# DisplayShieldV2.net
KiCad netlist of a schematic drawn in EAGLE
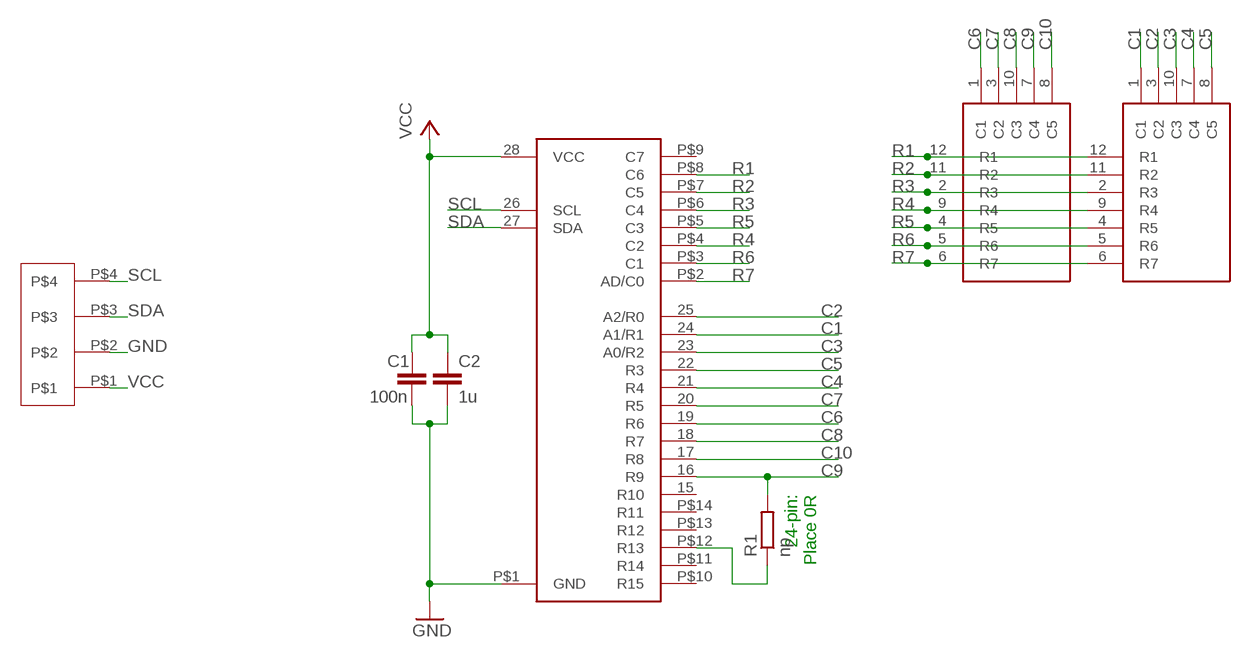
[diagram p0: schematic, sheet 1]

(export (version "E")
  (design (tool "Eeschema 10.0.6"))
  (components
    (comp (ref "C1")
      (value "100n")
      (footprint "eagle-import:C0603")
      (libsource (lib "eagle-import") (part "C-EUC0603"))
    )
    (comp (ref "C2")
      (value "1u")
      (footprint "eagle-import:C0603")
      (libsource (lib "eagle-import") (part "C-EUC0603"))
    )
    (comp (ref "R1")
      (value "np")
      (footprint "eagle-import:R0603")
      (libsource (lib "eagle-import") (part "R-EU_R0603"))
    )
    (comp (ref "U$1")
      (value "HT16K33A")
      (footprint "eagle-import:SSOP28")
      (libsource (lib "eagle-import") (part "HT16K33A"))
    )
    (comp (ref "U$2")
      (value "757A")
      (footprint "eagle-import:757A")
      (libsource (lib "eagle-import") (part "757A"))
    )
    (comp (ref "U$3")
      (value "757A")
      (footprint "eagle-import:757A")
      (libsource (lib "eagle-import") (part "757A"))
    )
    (comp (ref "U$4")
      (value "4P")
      (footprint "eagle-import:4PAD")
      (libsource (lib "eagle-import") (part "4P"))
    )
  )
  (nets
    (net (code "1") (name "/C1") (class "Default")
      (node (ref "U$1") (pin "24") (pinfunction "A1/R1_24") (pintype "bidirectional"))
      (node (ref "U$3") (pin "1") (pinfunction "C1_1") (pintype "bidirectional"))
    )
    (net (code "2") (name "/C2") (class "Default")
      (node (ref "U$1") (pin "25") (pinfunction "A2/R0_25") (pintype "bidirectional"))
      (node (ref "U$3") (pin "3") (pinfunction "C2_3") (pintype "bidirectional"))
    )
    (net (code "3") (name "/C3") (class "Default")
      (node (ref "U$1") (pin "23") (pinfunction "A0/R2_23") (pintype "bidirectional"))
      (node (ref "U$3") (pin "10") (pinfunction "C3_10") (pintype "bidirectional"))
    )
    (net (code "4") (name "/C4") (class "Default")
      (node (ref "U$1") (pin "21") (pinfunction "R4_21") (pintype "bidirectional"))
      (node (ref "U$3") (pin "7") (pinfunction "C4_7") (pintype "bidirectional"))
    )
    (net (code "5") (name "/C5") (class "Default")
      (node (ref "U$1") (pin "22") (pinfunction "R3_22") (pintype "bidirectional"))
      (node (ref "U$3") (pin "8") (pinfunction "C5_8") (pintype "bidirectional"))
    )
    (net (code "6") (name "/C6") (class "Default")
      (node (ref "U$1") (pin "19") (pinfunction "R6_19") (pintype "bidirectional"))
      (node (ref "U$2") (pin "1") (pinfunction "C1_1") (pintype "bidirectional"))
    )
    (net (code "7") (name "/C7") (class "Default")
      (node (ref "U$1") (pin "20") (pinfunction "R5_20") (pintype "bidirectional"))
      (node (ref "U$2") (pin "3") (pinfunction "C2_3") (pintype "bidirectional"))
    )
    (net (code "8") (name "/C8") (class "Default")
      (node (ref "U$1") (pin "18") (pinfunction "R7_18") (pintype "bidirectional"))
      (node (ref "U$2") (pin "10") (pinfunction "C3_10") (pintype "bidirectional"))
    )
    (net (code "9") (name "/C9") (class "Default")
      (node (ref "R1") (pin "2") (pinfunction "2_2") (pintype "passive"))
      (node (ref "U$1") (pin "16") (pinfunction "R9_16") (pintype "bidirectional"))
      (node (ref "U$2") (pin "7") (pinfunction "C4_7") (pintype "bidirectional"))
    )
    (net (code "10") (name "/C10") (class "Default")
      (node (ref "U$1") (pin "17") (pinfunction "R8_17") (pintype "bidirectional"))
      (node (ref "U$2") (pin "8") (pinfunction "C5_8") (pintype "bidirectional"))
    )
    (net (code "11") (name "/R1") (class "Default")
      (node (ref "U$1") (pin "P$8") (pinfunction "C6_P$8") (pintype "bidirectional"))
      (node (ref "U$2") (pin "12") (pinfunction "R1_12") (pintype "bidirectional"))
      (node (ref "U$3") (pin "12") (pinfunction "R1_12") (pintype "bidirectional"))
    )
    (net (code "12") (name "/R2") (class "Default")
      (node (ref "U$1") (pin "P$7") (pinfunction "C5_P$7") (pintype "bidirectional"))
      (node (ref "U$2") (pin "11") (pinfunction "R2_11") (pintype "bidirectional"))
      (node (ref "U$3") (pin "11") (pinfunction "R2_11") (pintype "bidirectional"))
    )
    (net (code "13") (name "/R3") (class "Default")
      (node (ref "U$1") (pin "P$6") (pinfunction "C4_P$6") (pintype "bidirectional"))
      (node (ref "U$2") (pin "2") (pinfunction "R3_2") (pintype "bidirectional"))
      (node (ref "U$3") (pin "2") (pinfunction "R3_2") (pintype "bidirectional"))
    )
    (net (code "14") (name "/R4") (class "Default")
      (node (ref "U$1") (pin "P$4") (pinfunction "C2_P$4") (pintype "bidirectional"))
      (node (ref "U$2") (pin "9") (pinfunction "R4_9") (pintype "bidirectional"))
      (node (ref "U$3") (pin "9") (pinfunction "R4_9") (pintype "bidirectional"))
    )
    (net (code "15") (name "/R5") (class "Default")
      (node (ref "U$1") (pin "P$5") (pinfunction "C3_P$5") (pintype "bidirectional"))
      (node (ref "U$2") (pin "4") (pinfunction "R5_4") (pintype "bidirectional"))
      (node (ref "U$3") (pin "4") (pinfunction "R5_4") (pintype "bidirectional"))
    )
    (net (code "16") (name "/R6") (class "Default")
      (node (ref "U$1") (pin "P$3") (pinfunction "C1_P$3") (pintype "bidirectional"))
      (node (ref "U$2") (pin "5") (pinfunction "R6_5") (pintype "bidirectional"))
      (node (ref "U$3") (pin "5") (pinfunction "R6_5") (pintype "bidirectional"))
    )
    (net (code "17") (name "/R7") (class "Default")
      (node (ref "U$1") (pin "P$2") (pinfunction "AD/C0_P$2") (pintype "bidirectional"))
      (node (ref "U$2") (pin "6") (pinfunction "R7_6") (pintype "bidirectional"))
      (node (ref "U$3") (pin "6") (pinfunction "R7_6") (pintype "bidirectional"))
    )
    (net (code "18") (name "/SCL") (class "Default")
      (node (ref "U$1") (pin "26") (pinfunction "SCL_26") (pintype "bidirectional"))
      (node (ref "U$4") (pin "P$4") (pinfunction "P$4_P$4") (pintype "bidirectional"))
    )
    (net (code "19") (name "/SDA") (class "Default")
      (node (ref "U$1") (pin "27") (pinfunction "SDA_27") (pintype "bidirectional"))
      (node (ref "U$4") (pin "P$3") (pinfunction "P$3_P$3") (pintype "bidirectional"))
    )
    (net (code "20") (name "GND") (class "Default")
      (node (ref "C1") (pin "2") (pinfunction "2_2") (pintype "passive"))
      (node (ref "C2") (pin "2") (pinfunction "2_2") (pintype "passive"))
      (node (ref "U$1") (pin "P$1") (pinfunction "GND_P$1") (pintype "power_in"))
      (node (ref "U$4") (pin "P$2") (pinfunction "P$2_P$2") (pintype "bidirectional"))
    )
    (net (code "21") (name "Net-(U$1-R13)") (class "Default")
      (node (ref "R1") (pin "1") (pinfunction "1_1") (pintype "passive"))
      (node (ref "U$1") (pin "P$12") (pinfunction "R13_P$12") (pintype "bidirectional"))
    )
    (net (code "22") (name "VCC") (class "Default")
      (node (ref "C1") (pin "1") (pinfunction "1_1") (pintype "passive"))
      (node (ref "C2") (pin "1") (pinfunction "1_1") (pintype "passive"))
      (node (ref "U$1") (pin "28") (pinfunction "VCC_28") (pintype "power_in"))
      (node (ref "U$4") (pin "P$1") (pinfunction "P$1_P$1") (pintype "bidirectional"))
    )
    (net (code "23") (name "unconnected-(U$1-C7-PadP$9)") (class "Default")
      (node (ref "U$1") (pin "P$9") (pinfunction "C7_P$9") (pintype "bidirectional"))
    )
    (net (code "24") (name "unconnected-(U$1-R10-Pad15)") (class "Default")
      (node (ref "U$1") (pin "15") (pinfunction "R10_15") (pintype "bidirectional"))
    )
    (net (code "25") (name "unconnected-(U$1-R11-PadP$14)") (class "Default")
      (node (ref "U$1") (pin "P$14") (pinfunction "R11_P$14") (pintype "bidirectional"))
    )
    (net (code "26") (name "unconnected-(U$1-R12-PadP$13)") (class "Default")
      (node (ref "U$1") (pin "P$13") (pinfunction "R12_P$13") (pintype "bidirectional"))
    )
    (net (code "27") (name "unconnected-(U$1-R14-PadP$11)") (class "Default")
      (node (ref "U$1") (pin "P$11") (pinfunction "R14_P$11") (pintype "bidirectional"))
    )
    (net (code "28") (name "unconnected-(U$1-R15-PadP$10)") (class "Default")
      (node (ref "U$1") (pin "P$10") (pinfunction "R15_P$10") (pintype "bidirectional"))
    )
  )
)
